# Lpc1114.net
KiCad netlist of a schematic drawn in EAGLE
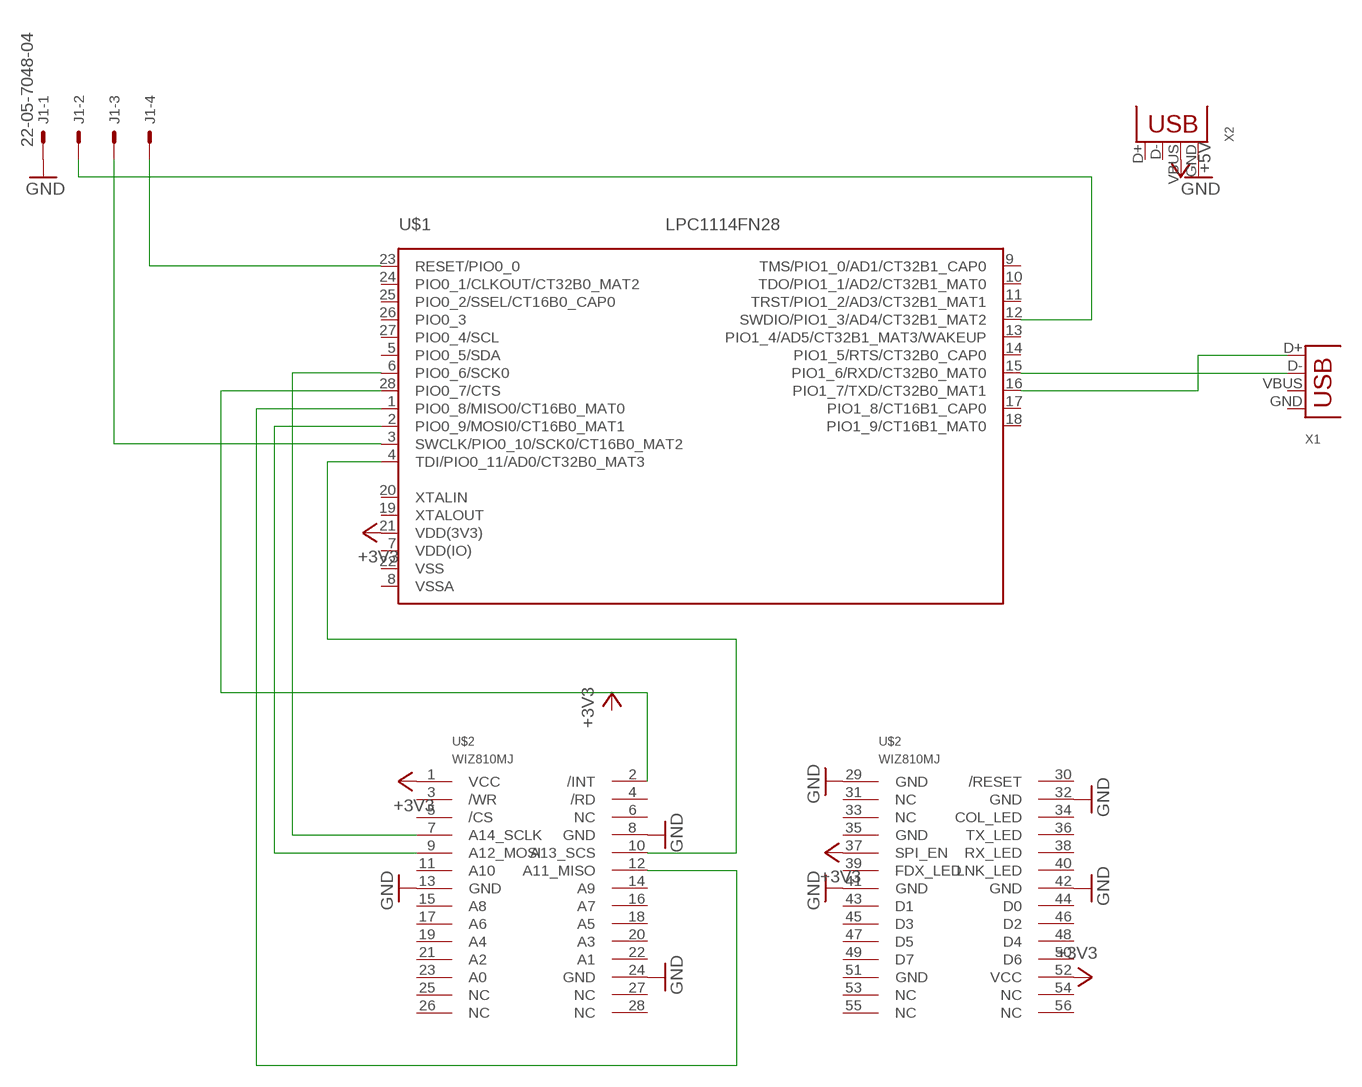
[diagram p0: schematic, sheet 1]

(export (version "E")
  (design (tool "Eeschema 10.0.6"))
  (components
    (comp (ref "J1")
      (value "22-05-7048-04")
      (footprint "eagle-import:7395-04")
      (libsource (lib "eagle-import") (part "22-?-0405-7048"))
    )
    (comp (ref "U$1")
      (value "LPC1114FN28")
      (footprint "eagle-import:DIP28")
      (libsource (lib "eagle-import") (part "LPC1114FN28"))
    )
    (comp (ref "U$2")
      (value "WIZ810MJ")
      (footprint "eagle-import:WIZ810MJ")
      (libsource (lib "eagle-import") (part "WIZ810MJ"))
    )
    (comp (ref "X1")
      (value "USB-A-H")
      (footprint "eagle-import:USB-A-H")
      (libsource (lib "eagle-import") (part "USB-A-H"))
    )
    (comp (ref "X2")
      (value "USB-B-H")
      (footprint "eagle-import:USB-B-H")
      (libsource (lib "eagle-import") (part "USB-B-H"))
    )
  )
  (nets
    (net (code "1") (name "+3V3") (class "Default")
      (node (ref "U$1") (pin "21") (pinfunction "VDD(3V3)_21") (pintype "power_in"))
      (node (ref "U$2") (pin "1") (pinfunction "VCC_1") (pintype "bidirectional"))
      (node (ref "U$2") (pin "37") (pinfunction "SPI_EN_37") (pintype "bidirectional"))
      (node (ref "U$2") (pin "52") (pinfunction "VCC_52") (pintype "bidirectional"))
    )
    (net (code "2") (name "+5V") (class "Default")
      (node (ref "X2") (pin "VBUS") (pinfunction "VBUS_VBUS") (pintype "bidirectional"))
    )
    (net (code "3") (name "/VDD(IO)") (class "Default")
      (node (ref "U$1") (pin "7") (pinfunction "VDD(IO)_7") (pintype "power_in"))
    )
    (net (code "4") (name "/VSS") (class "Default")
      (node (ref "U$1") (pin "22") (pinfunction "VSS_22") (pintype "power_in"))
    )
    (net (code "5") (name "/VSSA") (class "Default")
      (node (ref "U$1") (pin "8") (pinfunction "VSSA_8") (pintype "power_in"))
    )
    (net (code "6") (name "GND") (class "Default")
      (node (ref "J1") (pin "1") (pinfunction "S_1") (pintype "passive"))
      (node (ref "U$2") (pin "13") (pinfunction "GND_13") (pintype "bidirectional"))
      (node (ref "U$2") (pin "24") (pinfunction "GND_24") (pintype "bidirectional"))
      (node (ref "U$2") (pin "29") (pinfunction "GND_29") (pintype "bidirectional"))
      (node (ref "U$2") (pin "32") (pinfunction "GND_32") (pintype "bidirectional"))
      (node (ref "U$2") (pin "41") (pinfunction "GND_41") (pintype "bidirectional"))
      (node (ref "U$2") (pin "42") (pinfunction "GND_42") (pintype "bidirectional"))
      (node (ref "U$2") (pin "8") (pinfunction "GND_8") (pintype "bidirectional"))
      (node (ref "X2") (pin "GND") (pinfunction "GND_GND") (pintype "bidirectional"))
    )
    (net (code "7") (name "Net-(J1B-S)") (class "Default")
      (node (ref "J1") (pin "2") (pinfunction "S_2") (pintype "passive"))
      (node (ref "U$1") (pin "12") (pinfunction "SWDIO/PIO1_3/AD4/CT32B1_MAT2_12") (pintype "bidirectional"))
    )
    (net (code "8") (name "Net-(J1C-S)") (class "Default")
      (node (ref "J1") (pin "3") (pinfunction "S_3") (pintype "passive"))
      (node (ref "U$1") (pin "3") (pinfunction "SWCLK/PIO0_10/SCK0/CT16B0_MAT2_3") (pintype "bidirectional"))
    )
    (net (code "9") (name "Net-(J1D-S)") (class "Default")
      (node (ref "J1") (pin "4") (pinfunction "S_4") (pintype "passive"))
      (node (ref "U$1") (pin "23") (pinfunction "RESET/PIO0_0_23") (pintype "bidirectional"))
    )
    (net (code "10") (name "Net-(U$1-PIO0_6{slash}SCK0)") (class "Default")
      (node (ref "U$1") (pin "6") (pinfunction "PIO0_6/SCK0_6") (pintype "bidirectional"))
      (node (ref "U$2") (pin "7") (pinfunction "A14_SCLK_7") (pintype "bidirectional"))
    )
    (net (code "11") (name "Net-(U$1-PIO0_7{slash}CTS)") (class "Default")
      (node (ref "U$1") (pin "28") (pinfunction "PIO0_7/CTS_28") (pintype "bidirectional"))
      (node (ref "U$2") (pin "2") (pinfunction "/INT_2") (pintype "bidirectional"))
    )
    (net (code "12") (name "Net-(U$1-PIO0_8{slash}MISO0{slash}CT16B0_MAT0)") (class "Default")
      (node (ref "U$1") (pin "1") (pinfunction "PIO0_8/MISO0/CT16B0_MAT0_1") (pintype "bidirectional"))
      (node (ref "U$2") (pin "12") (pinfunction "A11_MISO_12") (pintype "bidirectional"))
    )
    (net (code "13") (name "Net-(U$1-PIO0_9{slash}MOSI0{slash}CT16B0_MAT1)") (class "Default")
      (node (ref "U$1") (pin "2") (pinfunction "PIO0_9/MOSI0/CT16B0_MAT1_2") (pintype "bidirectional"))
      (node (ref "U$2") (pin "9") (pinfunction "A12_MOSI_9") (pintype "bidirectional"))
    )
    (net (code "14") (name "Net-(U$1-PIO1_6{slash}RXD{slash}CT32B0_MAT0)") (class "Default")
      (node (ref "U$1") (pin "15") (pinfunction "PIO1_6/RXD/CT32B0_MAT0_15") (pintype "bidirectional"))
      (node (ref "X1") (pin "D-") (pinfunction "D-_D-") (pintype "bidirectional"))
    )
    (net (code "15") (name "Net-(U$1-PIO1_7{slash}TXD{slash}CT32B0_MAT1)") (class "Default")
      (node (ref "U$1") (pin "16") (pinfunction "PIO1_7/TXD/CT32B0_MAT1_16") (pintype "bidirectional"))
      (node (ref "X1") (pin "D+") (pinfunction "D+_D+") (pintype "bidirectional"))
    )
    (net (code "16") (name "Net-(U$1-TDI{slash}PIO0_11{slash}AD0{slash}CT32B0_MAT3)") (class "Default")
      (node (ref "U$1") (pin "4") (pinfunction "TDI/PIO0_11/AD0/CT32B0_MAT3_4") (pintype "bidirectional"))
      (node (ref "U$2") (pin "10") (pinfunction "A13_SCS_10") (pintype "bidirectional"))
    )
    (net (code "17") (name "unconnected-(U$1-PIO0_1{slash}CLKOUT{slash}CT32B0_MAT2-Pad24)") (class "Default")
      (node (ref "U$1") (pin "24") (pinfunction "PIO0_1/CLKOUT/CT32B0_MAT2_24") (pintype "bidirectional"))
    )
    (net (code "18") (name "unconnected-(U$1-PIO0_2{slash}SSEL{slash}CT16B0_CAP0-Pad25)") (class "Default")
      (node (ref "U$1") (pin "25") (pinfunction "PIO0_2/SSEL/CT16B0_CAP0_25") (pintype "bidirectional"))
    )
    (net (code "19") (name "unconnected-(U$1-PIO0_3-Pad26)") (class "Default")
      (node (ref "U$1") (pin "26") (pinfunction "PIO0_3_26") (pintype "bidirectional"))
    )
    (net (code "20") (name "unconnected-(U$1-PIO0_4{slash}SCL-Pad27)") (class "Default")
      (node (ref "U$1") (pin "27") (pinfunction "PIO0_4/SCL_27") (pintype "bidirectional"))
    )
    (net (code "21") (name "unconnected-(U$1-PIO0_5{slash}SDA-Pad5)") (class "Default")
      (node (ref "U$1") (pin "5") (pinfunction "PIO0_5/SDA_5") (pintype "bidirectional"))
    )
    (net (code "22") (name "unconnected-(U$1-PIO1_4{slash}AD5{slash}CT32B1_MAT3{slash}WAKEUP-Pad13)") (class "Default")
      (node (ref "U$1") (pin "13") (pinfunction "PIO1_4/AD5/CT32B1_MAT3/WAKEUP_13") (pintype "bidirectional"))
    )
    (net (code "23") (name "unconnected-(U$1-PIO1_5{slash}RTS{slash}CT32B0_CAP0-Pad14)") (class "Default")
      (node (ref "U$1") (pin "14") (pinfunction "PIO1_5/RTS/CT32B0_CAP0_14") (pintype "bidirectional"))
    )
    (net (code "24") (name "unconnected-(U$1-PIO1_8{slash}CT16B1_CAP0-Pad17)") (class "Default")
      (node (ref "U$1") (pin "17") (pinfunction "PIO1_8/CT16B1_CAP0_17") (pintype "bidirectional"))
    )
    (net (code "25") (name "unconnected-(U$1-PIO1_9{slash}CT16B1_MAT0-Pad18)") (class "Default")
      (node (ref "U$1") (pin "18") (pinfunction "PIO1_9/CT16B1_MAT0_18") (pintype "bidirectional"))
    )
    (net (code "26") (name "unconnected-(U$1-TDO{slash}PIO1_1{slash}AD2{slash}CT32B1_MAT0-Pad10)") (class "Default")
      (node (ref "U$1") (pin "10") (pinfunction "TDO/PIO1_1/AD2/CT32B1_MAT0_10") (pintype "bidirectional"))
    )
    (net (code "27") (name "unconnected-(U$1-TMS{slash}PIO1_0{slash}AD1{slash}CT32B1_CAP0-Pad9)") (class "Default")
      (node (ref "U$1") (pin "9") (pinfunction "TMS/PIO1_0/AD1/CT32B1_CAP0_9") (pintype "bidirectional"))
    )
    (net (code "28") (name "unconnected-(U$1-TRST{slash}PIO1_2{slash}AD3{slash}CT32B1_MAT1-Pad11)") (class "Default")
      (node (ref "U$1") (pin "11") (pinfunction "TRST/PIO1_2/AD3/CT32B1_MAT1_11") (pintype "bidirectional"))
    )
    (net (code "29") (name "unconnected-(U$1-XTALIN-Pad20)") (class "Default")
      (node (ref "U$1") (pin "20") (pinfunction "XTALIN_20") (pintype "input"))
    )
    (net (code "30") (name "unconnected-(U$1-XTALOUT-Pad19)") (class "Default")
      (node (ref "U$1") (pin "19") (pinfunction "XTALOUT_19") (pintype "output"))
    )
    (net (code "31") (name "unconnected-(U$2-A0-Pad23)") (class "Default")
      (node (ref "U$2") (pin "23") (pinfunction "A0_23") (pintype "bidirectional"))
    )
    (net (code "32") (name "unconnected-(U$2-A1-Pad22)") (class "Default")
      (node (ref "U$2") (pin "22") (pinfunction "A1_22") (pintype "bidirectional"))
    )
    (net (code "33") (name "unconnected-(U$2-A2-Pad21)") (class "Default")
      (node (ref "U$2") (pin "21") (pinfunction "A2_21") (pintype "bidirectional"))
    )
    (net (code "34") (name "unconnected-(U$2-A3-Pad20)") (class "Default")
      (node (ref "U$2") (pin "20") (pinfunction "A3_20") (pintype "bidirectional"))
    )
    (net (code "35") (name "unconnected-(U$2-A4-Pad19)") (class "Default")
      (node (ref "U$2") (pin "19") (pinfunction "A4_19") (pintype "bidirectional"))
    )
    (net (code "36") (name "unconnected-(U$2-A5-Pad18)") (class "Default")
      (node (ref "U$2") (pin "18") (pinfunction "A5_18") (pintype "bidirectional"))
    )
    (net (code "37") (name "unconnected-(U$2-A6-Pad17)") (class "Default")
      (node (ref "U$2") (pin "17") (pinfunction "A6_17") (pintype "bidirectional"))
    )
    (net (code "38") (name "unconnected-(U$2-A7-Pad16)") (class "Default")
      (node (ref "U$2") (pin "16") (pinfunction "A7_16") (pintype "bidirectional"))
    )
    (net (code "39") (name "unconnected-(U$2-A8-Pad15)") (class "Default")
      (node (ref "U$2") (pin "15") (pinfunction "A8_15") (pintype "bidirectional"))
    )
    (net (code "40") (name "unconnected-(U$2-A9-Pad14)") (class "Default")
      (node (ref "U$2") (pin "14") (pinfunction "A9_14") (pintype "bidirectional"))
    )
    (net (code "41") (name "unconnected-(U$2-A10-Pad11)") (class "Default")
      (node (ref "U$2") (pin "11") (pinfunction "A10_11") (pintype "bidirectional"))
    )
    (net (code "42") (name "unconnected-(U$2-COL_LED-Pad34)") (class "Default")
      (node (ref "U$2") (pin "34") (pinfunction "COL_LED_34") (pintype "bidirectional"))
    )
    (net (code "43") (name "unconnected-(U$2-D0-Pad44)") (class "Default")
      (node (ref "U$2") (pin "44") (pinfunction "D0_44") (pintype "bidirectional"))
    )
    (net (code "44") (name "unconnected-(U$2-D1-Pad43)") (class "Default")
      (node (ref "U$2") (pin "43") (pinfunction "D1_43") (pintype "bidirectional"))
    )
    (net (code "45") (name "unconnected-(U$2-D2-Pad46)") (class "Default")
      (node (ref "U$2") (pin "46") (pinfunction "D2_46") (pintype "bidirectional"))
    )
    (net (code "46") (name "unconnected-(U$2-D3-Pad45)") (class "Default")
      (node (ref "U$2") (pin "45") (pinfunction "D3_45") (pintype "bidirectional"))
    )
    (net (code "47") (name "unconnected-(U$2-D4-Pad48)") (class "Default")
      (node (ref "U$2") (pin "48") (pinfunction "D4_48") (pintype "bidirectional"))
    )
    (net (code "48") (name "unconnected-(U$2-D5-Pad47)") (class "Default")
      (node (ref "U$2") (pin "47") (pinfunction "D5_47") (pintype "bidirectional"))
    )
    (net (code "49") (name "unconnected-(U$2-D6-Pad50)") (class "Default")
      (node (ref "U$2") (pin "50") (pinfunction "D6_50") (pintype "bidirectional"))
    )
    (net (code "50") (name "unconnected-(U$2-D7-Pad49)") (class "Default")
      (node (ref "U$2") (pin "49") (pinfunction "D7_49") (pintype "bidirectional"))
    )
    (net (code "51") (name "unconnected-(U$2-FDX_LED-Pad39)") (class "Default")
      (node (ref "U$2") (pin "39") (pinfunction "FDX_LED_39") (pintype "bidirectional"))
    )
    (net (code "52") (name "unconnected-(U$2-GND-Pad35)") (class "Default")
      (node (ref "U$2") (pin "35") (pinfunction "GND_35") (pintype "bidirectional"))
    )
    (net (code "53") (name "unconnected-(U$2-GND-Pad51)") (class "Default")
      (node (ref "U$2") (pin "51") (pinfunction "GND_51") (pintype "bidirectional"))
    )
    (net (code "54") (name "unconnected-(U$2-LNK_LED-Pad40)") (class "Default")
      (node (ref "U$2") (pin "40") (pinfunction "LNK_LED_40") (pintype "bidirectional"))
    )
    (net (code "55") (name "unconnected-(U$2-NC-Pad6)") (class "Default")
      (node (ref "U$2") (pin "6") (pinfunction "NC_6") (pintype "bidirectional"))
    )
    (net (code "56") (name "unconnected-(U$2-NC-Pad25)") (class "Default")
      (node (ref "U$2") (pin "25") (pinfunction "NC_25") (pintype "bidirectional"))
    )
    (net (code "57") (name "unconnected-(U$2-NC-Pad26)") (class "Default")
      (node (ref "U$2") (pin "26") (pinfunction "NC_26") (pintype "bidirectional"))
    )
    (net (code "58") (name "unconnected-(U$2-NC-Pad27)") (class "Default")
      (node (ref "U$2") (pin "27") (pinfunction "NC_27") (pintype "bidirectional"))
    )
    (net (code "59") (name "unconnected-(U$2-NC-Pad28)") (class "Default")
      (node (ref "U$2") (pin "28") (pinfunction "NC_28") (pintype "bidirectional"))
    )
    (net (code "60") (name "unconnected-(U$2-NC-Pad31)") (class "Default")
      (node (ref "U$2") (pin "31") (pinfunction "NC_31") (pintype "bidirectional"))
    )
    (net (code "61") (name "unconnected-(U$2-NC-Pad33)") (class "Default")
      (node (ref "U$2") (pin "33") (pinfunction "NC_33") (pintype "bidirectional"))
    )
    (net (code "62") (name "unconnected-(U$2-NC-Pad53)") (class "Default")
      (node (ref "U$2") (pin "53") (pinfunction "NC_53") (pintype "bidirectional"))
    )
    (net (code "63") (name "unconnected-(U$2-NC-Pad54)") (class "Default")
      (node (ref "U$2") (pin "54") (pinfunction "NC_54") (pintype "bidirectional"))
    )
    (net (code "64") (name "unconnected-(U$2-NC-Pad55)") (class "Default")
      (node (ref "U$2") (pin "55") (pinfunction "NC_55") (pintype "bidirectional"))
    )
    (net (code "65") (name "unconnected-(U$2-NC-Pad56)") (class "Default")
      (node (ref "U$2") (pin "56") (pinfunction "NC_56") (pintype "bidirectional"))
    )
    (net (code "66") (name "unconnected-(U$2-RX_LED-Pad38)") (class "Default")
      (node (ref "U$2") (pin "38") (pinfunction "RX_LED_38") (pintype "bidirectional"))
    )
    (net (code "67") (name "unconnected-(U$2-TX_LED-Pad36)") (class "Default")
      (node (ref "U$2") (pin "36") (pinfunction "TX_LED_36") (pintype "bidirectional"))
    )
    (net (code "68") (name "unconnected-(U$2-{slash}CS-Pad5)") (class "Default")
      (node (ref "U$2") (pin "5") (pinfunction "/CS_5") (pintype "bidirectional"))
    )
    (net (code "69") (name "unconnected-(U$2-{slash}RD-Pad4)") (class "Default")
      (node (ref "U$2") (pin "4") (pinfunction "/RD_4") (pintype "bidirectional"))
    )
    (net (code "70") (name "unconnected-(U$2-{slash}RESET-Pad30)") (class "Default")
      (node (ref "U$2") (pin "30") (pinfunction "/RESET_30") (pintype "bidirectional"))
    )
    (net (code "71") (name "unconnected-(U$2-{slash}WR-Pad3)") (class "Default")
      (node (ref "U$2") (pin "3") (pinfunction "/WR_3") (pintype "bidirectional"))
    )
    (net (code "72") (name "unconnected-(X1-PadGND)") (class "Default")
      (node (ref "X1") (pin "GND") (pinfunction "GND_GND") (pintype "bidirectional"))
    )
    (net (code "73") (name "unconnected-(X1-PadVBUS)") (class "Default")
      (node (ref "X1") (pin "VBUS") (pinfunction "VBUS_VBUS") (pintype "bidirectional"))
    )
    (net (code "74") (name "unconnected-(X2-PadD+)") (class "Default")
      (node (ref "X2") (pin "D+") (pinfunction "D+_D+") (pintype "bidirectional"))
    )
    (net (code "75") (name "unconnected-(X2-PadD-)") (class "Default")
      (node (ref "X2") (pin "D-") (pinfunction "D-_D-") (pintype "bidirectional"))
    )
  )
)
